# POWER.net
KiCad netlist of a schematic drawn in Altium Designer
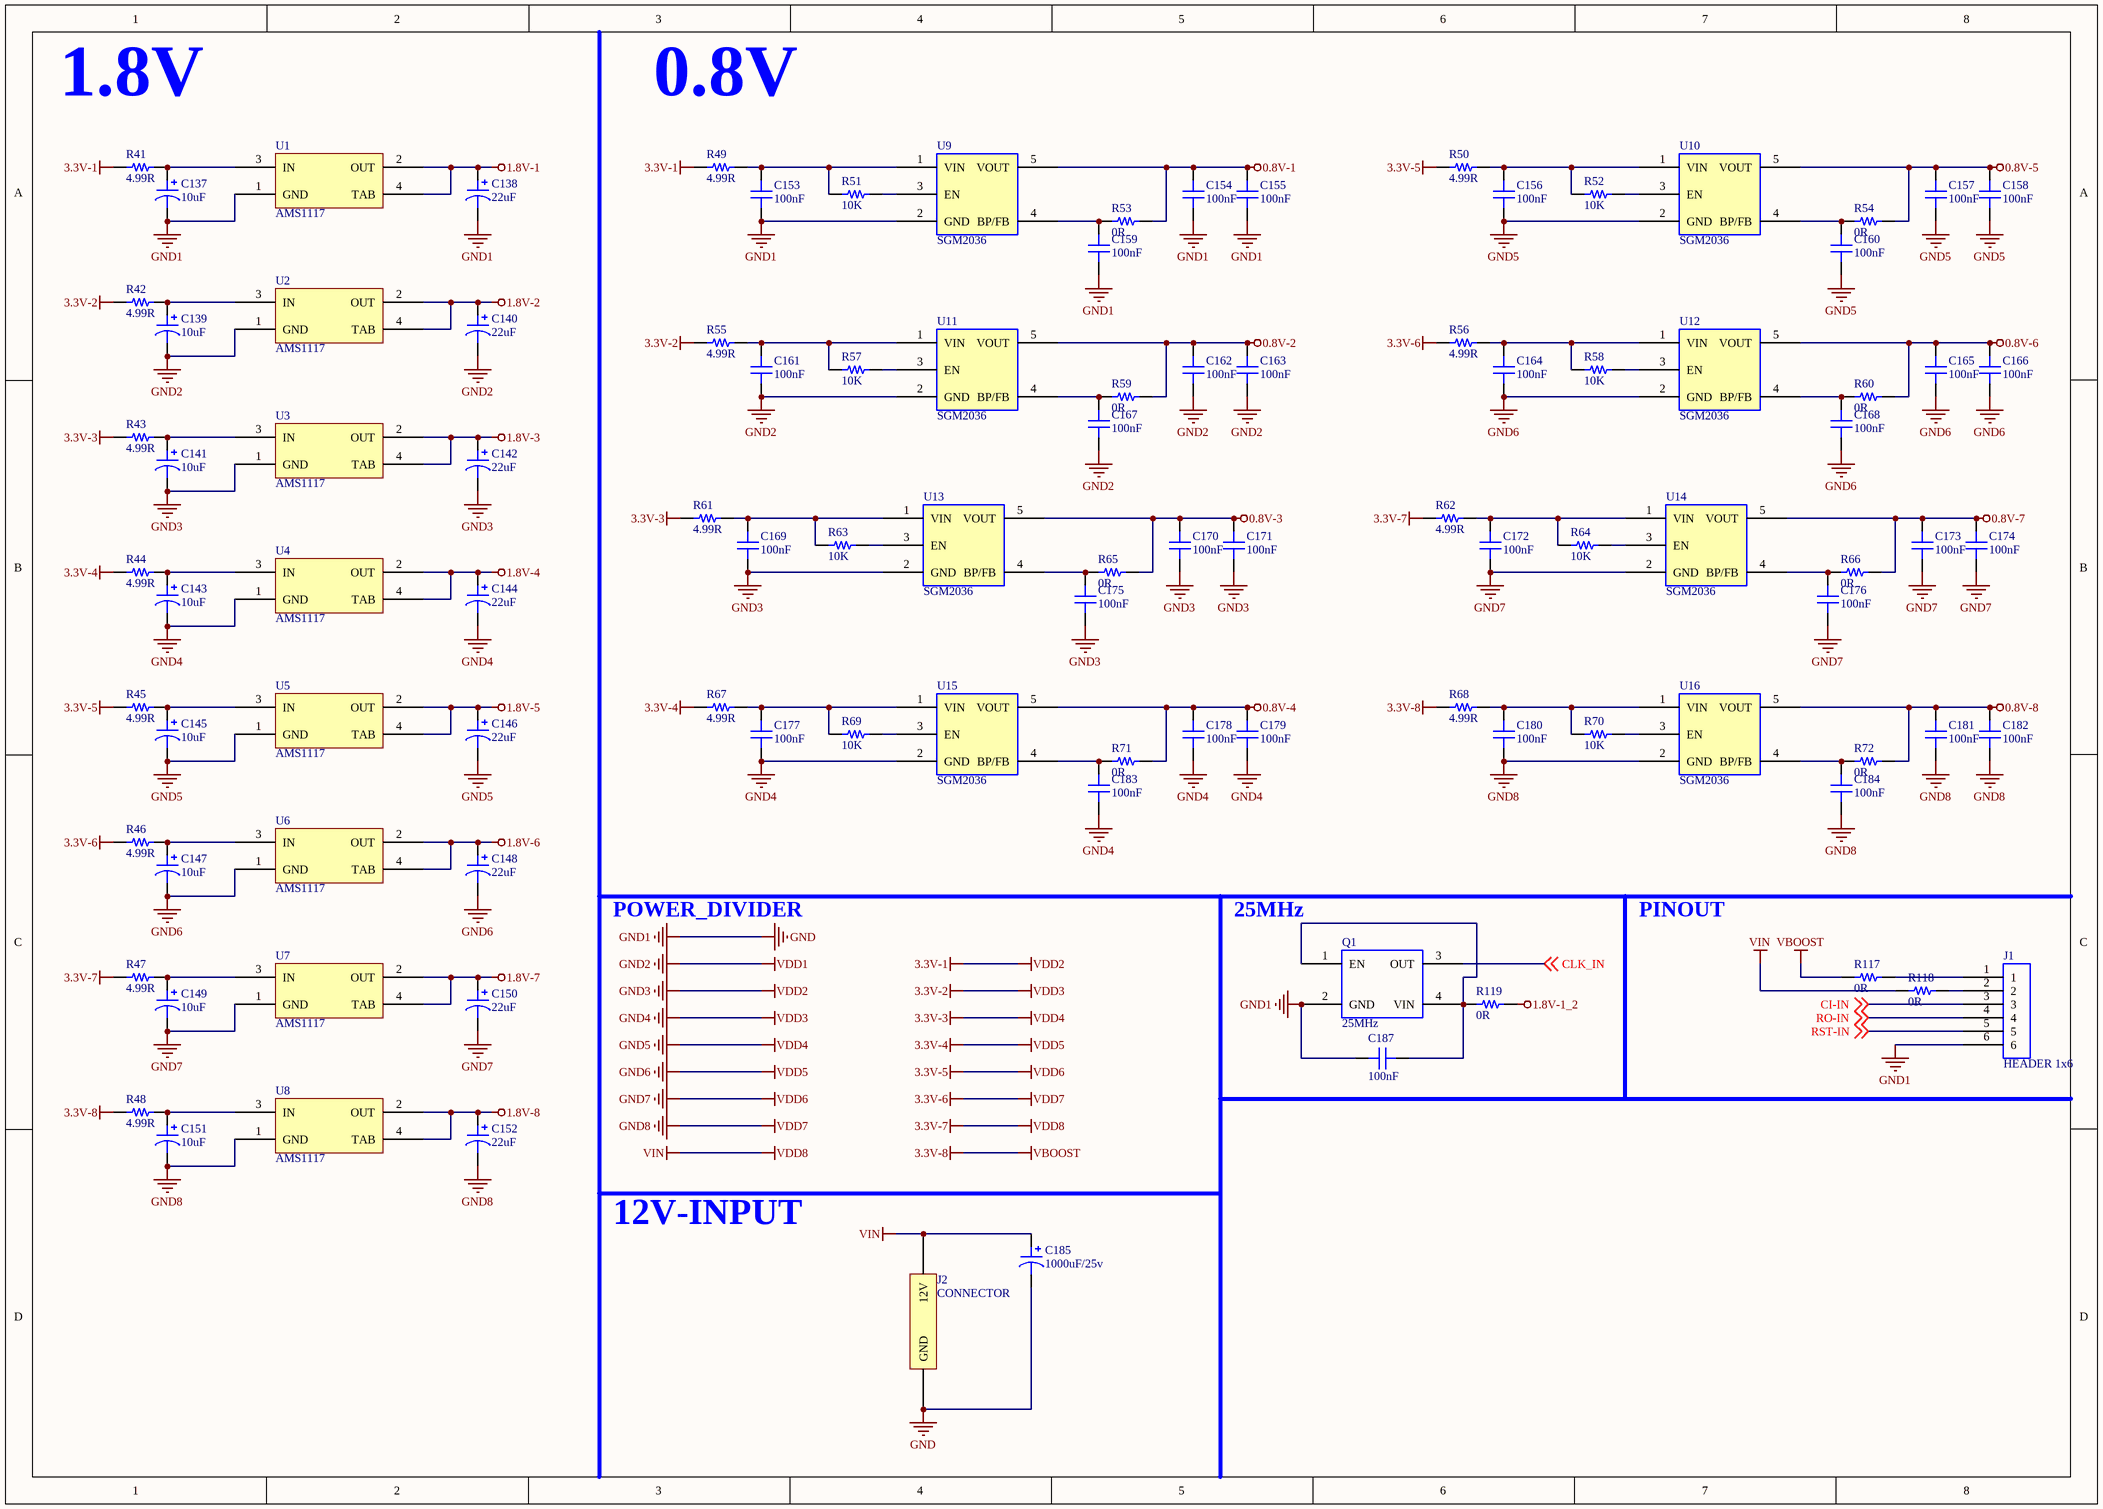
[diagram p0: POWER.SchDoc]

(export (version "E")
  (design (tool "Eeschema 10.0.6"))
  (components
    (comp (ref "C137")
      (value "10uF")
      (footprint "CAP-TAN-CASE-A")
      (libsource (lib "Miner-8Chips") (part "POLARIZED CAP"))
    )
    (comp (ref "C138")
      (value "22uF")
      (footprint "CAP-TAN-CASE-A")
      (libsource (lib "Miner-8Chips") (part "POLARIZED CAP"))
    )
    (comp (ref "C139")
      (value "10uF")
      (footprint "CAP-TAN-CASE-A")
      (libsource (lib "Miner-8Chips") (part "POLARIZED CAP"))
    )
    (comp (ref "C140")
      (value "22uF")
      (footprint "CAP-TAN-CASE-A")
      (libsource (lib "Miner-8Chips") (part "POLARIZED CAP"))
    )
    (comp (ref "C141")
      (value "10uF")
      (footprint "CAP-TAN-CASE-A")
      (libsource (lib "Miner-8Chips") (part "POLARIZED CAP"))
    )
    (comp (ref "C142")
      (value "22uF")
      (footprint "CAP-TAN-CASE-A")
      (libsource (lib "Miner-8Chips") (part "POLARIZED CAP"))
    )
    (comp (ref "C143")
      (value "10uF")
      (footprint "CAP-TAN-CASE-A")
      (libsource (lib "Miner-8Chips") (part "POLARIZED CAP"))
    )
    (comp (ref "C144")
      (value "22uF")
      (footprint "CAP-TAN-CASE-A")
      (libsource (lib "Miner-8Chips") (part "POLARIZED CAP"))
    )
    (comp (ref "C145")
      (value "10uF")
      (footprint "CAP-TAN-CASE-A")
      (libsource (lib "Miner-8Chips") (part "POLARIZED CAP"))
    )
    (comp (ref "C146")
      (value "22uF")
      (footprint "CAP-TAN-CASE-A")
      (libsource (lib "Miner-8Chips") (part "POLARIZED CAP"))
    )
    (comp (ref "C147")
      (value "10uF")
      (footprint "CAP-TAN-CASE-A")
      (libsource (lib "Miner-8Chips") (part "POLARIZED CAP"))
    )
    (comp (ref "C148")
      (value "22uF")
      (footprint "CAP-TAN-CASE-A")
      (libsource (lib "Miner-8Chips") (part "POLARIZED CAP"))
    )
    (comp (ref "C149")
      (value "10uF")
      (footprint "CAP-TAN-CASE-A")
      (libsource (lib "Miner-8Chips") (part "POLARIZED CAP"))
    )
    (comp (ref "C150")
      (value "22uF")
      (footprint "CAP-TAN-CASE-A")
      (libsource (lib "Miner-8Chips") (part "POLARIZED CAP"))
    )
    (comp (ref "C151")
      (value "10uF")
      (footprint "CAP-TAN-CASE-A")
      (libsource (lib "Miner-8Chips") (part "POLARIZED CAP"))
    )
    (comp (ref "C152")
      (value "22uF")
      (footprint "CAP-TAN-CASE-A")
      (libsource (lib "Miner-8Chips") (part "POLARIZED CAP"))
    )
    (comp (ref "C153")
      (value "100nF")
      (footprint "CAP-SMD-0402")
      (libsource (lib "Miner-8Chips") (part "CAP"))
    )
    (comp (ref "C154")
      (value "100nF")
      (footprint "CAP-SMD-0402")
      (libsource (lib "Miner-8Chips") (part "CAP"))
    )
    (comp (ref "C155")
      (value "100nF")
      (footprint "CAP-SMD-0402")
      (libsource (lib "Miner-8Chips") (part "CAP"))
    )
    (comp (ref "C156")
      (value "100nF")
      (footprint "CAP-SMD-0402")
      (libsource (lib "Miner-8Chips") (part "CAP"))
    )
    (comp (ref "C157")
      (value "100nF")
      (footprint "CAP-SMD-0402")
      (libsource (lib "Miner-8Chips") (part "CAP"))
    )
    (comp (ref "C158")
      (value "100nF")
      (footprint "CAP-SMD-0402")
      (libsource (lib "Miner-8Chips") (part "CAP"))
    )
    (comp (ref "C159")
      (value "100nF")
      (footprint "CAP-SMD-0402")
      (libsource (lib "Miner-8Chips") (part "CAP"))
    )
    (comp (ref "C160")
      (value "100nF")
      (footprint "CAP-SMD-0402")
      (libsource (lib "Miner-8Chips") (part "CAP"))
    )
    (comp (ref "C161")
      (value "100nF")
      (footprint "CAP-SMD-0402")
      (libsource (lib "Miner-8Chips") (part "CAP"))
    )
    (comp (ref "C162")
      (value "100nF")
      (footprint "CAP-SMD-0402")
      (libsource (lib "Miner-8Chips") (part "CAP"))
    )
    (comp (ref "C163")
      (value "100nF")
      (footprint "CAP-SMD-0402")
      (libsource (lib "Miner-8Chips") (part "CAP"))
    )
    (comp (ref "C164")
      (value "100nF")
      (footprint "CAP-SMD-0402")
      (libsource (lib "Miner-8Chips") (part "CAP"))
    )
    (comp (ref "C165")
      (value "100nF")
      (footprint "CAP-SMD-0402")
      (libsource (lib "Miner-8Chips") (part "CAP"))
    )
    (comp (ref "C166")
      (value "100nF")
      (footprint "CAP-SMD-0402")
      (libsource (lib "Miner-8Chips") (part "CAP"))
    )
    (comp (ref "C167")
      (value "100nF")
      (footprint "CAP-SMD-0402")
      (libsource (lib "Miner-8Chips") (part "CAP"))
    )
    (comp (ref "C168")
      (value "100nF")
      (footprint "CAP-SMD-0402")
      (libsource (lib "Miner-8Chips") (part "CAP"))
    )
    (comp (ref "C169")
      (value "100nF")
      (footprint "CAP-SMD-0402")
      (libsource (lib "Miner-8Chips") (part "CAP"))
    )
    (comp (ref "C170")
      (value "100nF")
      (footprint "CAP-SMD-0402")
      (libsource (lib "Miner-8Chips") (part "CAP"))
    )
    (comp (ref "C171")
      (value "100nF")
      (footprint "CAP-SMD-0402")
      (libsource (lib "Miner-8Chips") (part "CAP"))
    )
    (comp (ref "C172")
      (value "100nF")
      (footprint "CAP-SMD-0402")
      (libsource (lib "Miner-8Chips") (part "CAP"))
    )
    (comp (ref "C173")
      (value "100nF")
      (footprint "CAP-SMD-0402")
      (libsource (lib "Miner-8Chips") (part "CAP"))
    )
    (comp (ref "C174")
      (value "100nF")
      (footprint "CAP-SMD-0402")
      (libsource (lib "Miner-8Chips") (part "CAP"))
    )
    (comp (ref "C175")
      (value "100nF")
      (footprint "CAP-SMD-0402")
      (libsource (lib "Miner-8Chips") (part "CAP"))
    )
    (comp (ref "C176")
      (value "100nF")
      (footprint "CAP-SMD-0402")
      (libsource (lib "Miner-8Chips") (part "CAP"))
    )
    (comp (ref "C177")
      (value "100nF")
      (footprint "CAP-SMD-0402")
      (libsource (lib "Miner-8Chips") (part "CAP"))
    )
    (comp (ref "C178")
      (value "100nF")
      (footprint "CAP-SMD-0402")
      (libsource (lib "Miner-8Chips") (part "CAP"))
    )
    (comp (ref "C179")
      (value "100nF")
      (footprint "CAP-SMD-0402")
      (libsource (lib "Miner-8Chips") (part "CAP"))
    )
    (comp (ref "C180")
      (value "100nF")
      (footprint "CAP-SMD-0402")
      (libsource (lib "Miner-8Chips") (part "CAP"))
    )
    (comp (ref "C181")
      (value "100nF")
      (footprint "CAP-SMD-0402")
      (libsource (lib "Miner-8Chips") (part "CAP"))
    )
    (comp (ref "C182")
      (value "100nF")
      (footprint "CAP-SMD-0402")
      (libsource (lib "Miner-8Chips") (part "CAP"))
    )
    (comp (ref "C183")
      (value "100nF")
      (footprint "CAP-SMD-0402")
      (libsource (lib "Miner-8Chips") (part "CAP"))
    )
    (comp (ref "C184")
      (value "100nF")
      (footprint "CAP-SMD-0402")
      (libsource (lib "Miner-8Chips") (part "CAP"))
    )
    (comp (ref "C185")
      (value "1000uF/25v")
      (footprint "CAP ALUM 10.3MM")
      (libsource (lib "Miner-8Chips") (part "POLARIZED CAP"))
    )
    (comp (ref "C187")
      (value "100nF")
      (footprint "CAP-SMD-0603")
      (libsource (lib "Miner-8Chips") (part "CAP"))
    )
    (comp (ref "J1")
      (value "HEADER 1x6")
      (footprint "HEADER-1x6")
      (libsource (lib "Miner-8Chips") (part "HEADER 1x6"))
    )
    (comp (ref "J2") (value "CONNECTOR") (footprint "ATX 6") (libsource (lib "Miner-8Chips") (part "ATX 6")))
    (comp (ref "Q1") (value "25MHz") (footprint "XTALL") (libsource (lib "Miner-8Chips") (part "OSCILLATOR")))
    (comp (ref "R41")
      (value "4.99R")
      (footprint "RES-SMD-1206")
      (libsource (lib "Miner-8Chips") (part "RES"))
    )
    (comp (ref "R42")
      (value "4.99R")
      (footprint "RES-SMD-1206")
      (libsource (lib "Miner-8Chips") (part "RES"))
    )
    (comp (ref "R43")
      (value "4.99R")
      (footprint "RES-SMD-1206")
      (libsource (lib "Miner-8Chips") (part "RES"))
    )
    (comp (ref "R44")
      (value "4.99R")
      (footprint "RES-SMD-1206")
      (libsource (lib "Miner-8Chips") (part "RES"))
    )
    (comp (ref "R45")
      (value "4.99R")
      (footprint "RES-SMD-1206")
      (libsource (lib "Miner-8Chips") (part "RES"))
    )
    (comp (ref "R46")
      (value "4.99R")
      (footprint "RES-SMD-1206")
      (libsource (lib "Miner-8Chips") (part "RES"))
    )
    (comp (ref "R47")
      (value "4.99R")
      (footprint "RES-SMD-1206")
      (libsource (lib "Miner-8Chips") (part "RES"))
    )
    (comp (ref "R48")
      (value "4.99R")
      (footprint "RES-SMD-1206")
      (libsource (lib "Miner-8Chips") (part "RES"))
    )
    (comp (ref "R49")
      (value "4.99R")
      (footprint "RES-SMD-1206")
      (libsource (lib "Miner-8Chips") (part "RES"))
    )
    (comp (ref "R50")
      (value "4.99R")
      (footprint "RES-SMD-1206")
      (libsource (lib "Miner-8Chips") (part "RES"))
    )
    (comp (ref "R51") (value "10K") (footprint "RES-SMD-0402") (libsource (lib "Miner-8Chips") (part "RES")))
    (comp (ref "R52") (value "10K") (footprint "RES-SMD-0402") (libsource (lib "Miner-8Chips") (part "RES")))
    (comp (ref "R53") (value "0R") (footprint "RES-SMD-0402") (libsource (lib "Miner-8Chips") (part "RES")))
    (comp (ref "R54") (value "0R") (footprint "RES-SMD-0402") (libsource (lib "Miner-8Chips") (part "RES")))
    (comp (ref "R55")
      (value "4.99R")
      (footprint "RES-SMD-1206")
      (libsource (lib "Miner-8Chips") (part "RES"))
    )
    (comp (ref "R56")
      (value "4.99R")
      (footprint "RES-SMD-1206")
      (libsource (lib "Miner-8Chips") (part "RES"))
    )
    (comp (ref "R57") (value "10K") (footprint "RES-SMD-0402") (libsource (lib "Miner-8Chips") (part "RES")))
    (comp (ref "R58") (value "10K") (footprint "RES-SMD-0402") (libsource (lib "Miner-8Chips") (part "RES")))
    (comp (ref "R59") (value "0R") (footprint "RES-SMD-0402") (libsource (lib "Miner-8Chips") (part "RES")))
    (comp (ref "R60") (value "0R") (footprint "RES-SMD-0402") (libsource (lib "Miner-8Chips") (part "RES")))
    (comp (ref "R61")
      (value "4.99R")
      (footprint "RES-SMD-1206")
      (libsource (lib "Miner-8Chips") (part "RES"))
    )
    (comp (ref "R62")
      (value "4.99R")
      (footprint "RES-SMD-1206")
      (libsource (lib "Miner-8Chips") (part "RES"))
    )
    (comp (ref "R63") (value "10K") (footprint "RES-SMD-0402") (libsource (lib "Miner-8Chips") (part "RES")))
    (comp (ref "R64") (value "10K") (footprint "RES-SMD-0402") (libsource (lib "Miner-8Chips") (part "RES")))
    (comp (ref "R65") (value "0R") (footprint "RES-SMD-0402") (libsource (lib "Miner-8Chips") (part "RES")))
    (comp (ref "R66") (value "0R") (footprint "RES-SMD-0402") (libsource (lib "Miner-8Chips") (part "RES")))
    (comp (ref "R67")
      (value "4.99R")
      (footprint "RES-SMD-1206")
      (libsource (lib "Miner-8Chips") (part "RES"))
    )
    (comp (ref "R68")
      (value "4.99R")
      (footprint "RES-SMD-1206")
      (libsource (lib "Miner-8Chips") (part "RES"))
    )
    (comp (ref "R69") (value "10K") (footprint "RES-SMD-0402") (libsource (lib "Miner-8Chips") (part "RES")))
    (comp (ref "R70") (value "10K") (footprint "RES-SMD-0402") (libsource (lib "Miner-8Chips") (part "RES")))
    (comp (ref "R71") (value "0R") (footprint "RES-SMD-0402") (libsource (lib "Miner-8Chips") (part "RES")))
    (comp (ref "R72") (value "0R") (footprint "RES-SMD-0402") (libsource (lib "Miner-8Chips") (part "RES")))
    (comp (ref "R117") (value "0R") (footprint "RES") (libsource (lib "Miner-8Chips") (part "RES")))
    (comp (ref "R118") (value "0R") (footprint "RES") (libsource (lib "Miner-8Chips") (part "RES")))
    (comp (ref "R119") (value "0R") (footprint "RES") (libsource (lib "Miner-8Chips") (part "RES")))
    (comp (ref "U1")
      (value "AMS1117")
      (footprint "AMS1117")
      (libsource (lib "Miner-8Chips") (part "AMS1117"))
    )
    (comp (ref "U2")
      (value "AMS1117")
      (footprint "AMS1117")
      (libsource (lib "Miner-8Chips") (part "AMS1117"))
    )
    (comp (ref "U3")
      (value "AMS1117")
      (footprint "AMS1117")
      (libsource (lib "Miner-8Chips") (part "AMS1117"))
    )
    (comp (ref "U4")
      (value "AMS1117")
      (footprint "AMS1117")
      (libsource (lib "Miner-8Chips") (part "AMS1117"))
    )
    (comp (ref "U5")
      (value "AMS1117")
      (footprint "AMS1117")
      (libsource (lib "Miner-8Chips") (part "AMS1117"))
    )
    (comp (ref "U6")
      (value "AMS1117")
      (footprint "AMS1117")
      (libsource (lib "Miner-8Chips") (part "AMS1117"))
    )
    (comp (ref "U7")
      (value "AMS1117")
      (footprint "AMS1117")
      (libsource (lib "Miner-8Chips") (part "AMS1117"))
    )
    (comp (ref "U8")
      (value "AMS1117")
      (footprint "AMS1117")
      (libsource (lib "Miner-8Chips") (part "AMS1117"))
    )
    (comp (ref "U9")
      (value "SGM2036")
      (footprint "SOT23-5PIN")
      (libsource (lib "Miner-8Chips") (part "SGM2036"))
    )
    (comp (ref "U10")
      (value "SGM2036")
      (footprint "SOT23-5PIN")
      (libsource (lib "Miner-8Chips") (part "SGM2036"))
    )
    (comp (ref "U11")
      (value "SGM2036")
      (footprint "SOT23-5PIN")
      (libsource (lib "Miner-8Chips") (part "SGM2036"))
    )
    (comp (ref "U12")
      (value "SGM2036")
      (footprint "SOT23-5PIN")
      (libsource (lib "Miner-8Chips") (part "SGM2036"))
    )
    (comp (ref "U13")
      (value "SGM2036")
      (footprint "SOT23-5PIN")
      (libsource (lib "Miner-8Chips") (part "SGM2036"))
    )
    (comp (ref "U14")
      (value "SGM2036")
      (footprint "SOT23-5PIN")
      (libsource (lib "Miner-8Chips") (part "SGM2036"))
    )
    (comp (ref "U15")
      (value "SGM2036")
      (footprint "SOT23-5PIN")
      (libsource (lib "Miner-8Chips") (part "SGM2036"))
    )
    (comp (ref "U16")
      (value "SGM2036")
      (footprint "SOT23-5PIN")
      (libsource (lib "Miner-8Chips") (part "SGM2036"))
    )
  )
  (nets
    (net (code "1") (name "0.8V-1") (class "Default")
      (node (ref "C154") (pin "2") (pinfunction "2_2") (pintype "passive"))
      (node (ref "C155") (pin "2") (pinfunction "2_2") (pintype "passive"))
      (node (ref "R53") (pin "2") (pinfunction "2_2") (pintype "passive"))
      (node (ref "U9") (pin "5") (pinfunction "VOUT_5") (pintype "passive"))
    )
    (net (code "2") (name "0.8V-2") (class "Default")
      (node (ref "C162") (pin "2") (pinfunction "2_2") (pintype "passive"))
      (node (ref "C163") (pin "2") (pinfunction "2_2") (pintype "passive"))
      (node (ref "R59") (pin "2") (pinfunction "2_2") (pintype "passive"))
      (node (ref "U11") (pin "5") (pinfunction "VOUT_5") (pintype "passive"))
    )
    (net (code "3") (name "0.8V-3") (class "Default")
      (node (ref "C170") (pin "2") (pinfunction "2_2") (pintype "passive"))
      (node (ref "C171") (pin "2") (pinfunction "2_2") (pintype "passive"))
      (node (ref "R65") (pin "2") (pinfunction "2_2") (pintype "passive"))
      (node (ref "U13") (pin "5") (pinfunction "VOUT_5") (pintype "passive"))
    )
    (net (code "4") (name "0.8V-4") (class "Default")
      (node (ref "C178") (pin "2") (pinfunction "2_2") (pintype "passive"))
      (node (ref "C179") (pin "2") (pinfunction "2_2") (pintype "passive"))
      (node (ref "R71") (pin "2") (pinfunction "2_2") (pintype "passive"))
      (node (ref "U15") (pin "5") (pinfunction "VOUT_5") (pintype "passive"))
    )
    (net (code "5") (name "0.8V-5") (class "Default")
      (node (ref "C157") (pin "2") (pinfunction "2_2") (pintype "passive"))
      (node (ref "C158") (pin "2") (pinfunction "2_2") (pintype "passive"))
      (node (ref "R54") (pin "2") (pinfunction "2_2") (pintype "passive"))
      (node (ref "U10") (pin "5") (pinfunction "VOUT_5") (pintype "passive"))
    )
    (net (code "6") (name "0.8V-6") (class "Default")
      (node (ref "C165") (pin "2") (pinfunction "2_2") (pintype "passive"))
      (node (ref "C166") (pin "2") (pinfunction "2_2") (pintype "passive"))
      (node (ref "R60") (pin "2") (pinfunction "2_2") (pintype "passive"))
      (node (ref "U12") (pin "5") (pinfunction "VOUT_5") (pintype "passive"))
    )
    (net (code "7") (name "0.8V-7") (class "Default")
      (node (ref "C173") (pin "2") (pinfunction "2_2") (pintype "passive"))
      (node (ref "C174") (pin "2") (pinfunction "2_2") (pintype "passive"))
      (node (ref "R66") (pin "2") (pinfunction "2_2") (pintype "passive"))
      (node (ref "U14") (pin "5") (pinfunction "VOUT_5") (pintype "passive"))
    )
    (net (code "8") (name "0.8V-8") (class "Default")
      (node (ref "C181") (pin "2") (pinfunction "2_2") (pintype "passive"))
      (node (ref "C182") (pin "2") (pinfunction "2_2") (pintype "passive"))
      (node (ref "R72") (pin "2") (pinfunction "2_2") (pintype "passive"))
      (node (ref "U16") (pin "5") (pinfunction "VOUT_5") (pintype "passive"))
    )
    (net (code "9") (name "1.8V-1") (class "Default")
      (node (ref "C138") (pin "1") (pinfunction "1_1") (pintype "passive"))
      (node (ref "U1") (pin "2") (pinfunction "OUT_2") (pintype "passive"))
      (node (ref "U1") (pin "4") (pinfunction "TAB_4") (pintype "passive"))
    )
    (net (code "10") (name "1.8V-1_2") (class "Default")
      (node (ref "R119") (pin "2") (pinfunction "2_2") (pintype "passive"))
    )
    (net (code "11") (name "1.8V-2") (class "Default")
      (node (ref "C140") (pin "1") (pinfunction "1_1") (pintype "passive"))
      (node (ref "U2") (pin "2") (pinfunction "OUT_2") (pintype "passive"))
      (node (ref "U2") (pin "4") (pinfunction "TAB_4") (pintype "passive"))
    )
    (net (code "12") (name "1.8V-3") (class "Default")
      (node (ref "C142") (pin "1") (pinfunction "1_1") (pintype "passive"))
      (node (ref "U3") (pin "2") (pinfunction "OUT_2") (pintype "passive"))
      (node (ref "U3") (pin "4") (pinfunction "TAB_4") (pintype "passive"))
    )
    (net (code "13") (name "1.8V-4") (class "Default")
      (node (ref "C144") (pin "1") (pinfunction "1_1") (pintype "passive"))
      (node (ref "U4") (pin "2") (pinfunction "OUT_2") (pintype "passive"))
      (node (ref "U4") (pin "4") (pinfunction "TAB_4") (pintype "passive"))
    )
    (net (code "14") (name "1.8V-5") (class "Default")
      (node (ref "C146") (pin "1") (pinfunction "1_1") (pintype "passive"))
      (node (ref "U5") (pin "2") (pinfunction "OUT_2") (pintype "passive"))
      (node (ref "U5") (pin "4") (pinfunction "TAB_4") (pintype "passive"))
    )
    (net (code "15") (name "1.8V-6") (class "Default")
      (node (ref "C148") (pin "1") (pinfunction "1_1") (pintype "passive"))
      (node (ref "U6") (pin "2") (pinfunction "OUT_2") (pintype "passive"))
      (node (ref "U6") (pin "4") (pinfunction "TAB_4") (pintype "passive"))
    )
    (net (code "16") (name "1.8V-7") (class "Default")
      (node (ref "C150") (pin "1") (pinfunction "1_1") (pintype "passive"))
      (node (ref "U7") (pin "2") (pinfunction "OUT_2") (pintype "passive"))
      (node (ref "U7") (pin "4") (pinfunction "TAB_4") (pintype "passive"))
    )
    (net (code "17") (name "1.8V-8") (class "Default")
      (node (ref "C152") (pin "1") (pinfunction "1_1") (pintype "passive"))
      (node (ref "U8") (pin "2") (pinfunction "OUT_2") (pintype "passive"))
      (node (ref "U8") (pin "4") (pinfunction "TAB_4") (pintype "passive"))
    )
    (net (code "18") (name "3.3V-1") (class "Default")
      (node (ref "C141") (pin "2") (pinfunction "2_2") (pintype "passive"))
      (node (ref "C142") (pin "2") (pinfunction "2_2") (pintype "passive"))
      (node (ref "C169") (pin "1") (pinfunction "1_1") (pintype "passive"))
      (node (ref "C170") (pin "1") (pinfunction "1_1") (pintype "passive"))
      (node (ref "C171") (pin "1") (pinfunction "1_1") (pintype "passive"))
      (node (ref "C175") (pin "1") (pinfunction "1_1") (pintype "passive"))
      (node (ref "R41") (pin "1") (pinfunction "1_1") (pintype "passive"))
      (node (ref "R49") (pin "1") (pinfunction "1_1") (pintype "passive"))
      (node (ref "U13") (pin "2") (pinfunction "GND_2") (pintype "passive"))
      (node (ref "U3") (pin "1") (pinfunction "GND_1") (pintype "passive"))
    )
    (net (code "19") (name "3.3V-2") (class "Default")
      (node (ref "C143") (pin "2") (pinfunction "2_2") (pintype "passive"))
      (node (ref "C144") (pin "2") (pinfunction "2_2") (pintype "passive"))
      (node (ref "C177") (pin "1") (pinfunction "1_1") (pintype "passive"))
      (node (ref "C178") (pin "1") (pinfunction "1_1") (pintype "passive"))
      (node (ref "C179") (pin "1") (pinfunction "1_1") (pintype "passive"))
      (node (ref "C183") (pin "1") (pinfunction "1_1") (pintype "passive"))
      (node (ref "R42") (pin "1") (pinfunction "1_1") (pintype "passive"))
      (node (ref "R55") (pin "1") (pinfunction "1_1") (pintype "passive"))
      (node (ref "U15") (pin "2") (pinfunction "GND_2") (pintype "passive"))
      (node (ref "U4") (pin "1") (pinfunction "GND_1") (pintype "passive"))
    )
    (net (code "20") (name "3.3V-3") (class "Default")
      (node (ref "C145") (pin "2") (pinfunction "2_2") (pintype "passive"))
      (node (ref "C146") (pin "2") (pinfunction "2_2") (pintype "passive"))
      (node (ref "C156") (pin "1") (pinfunction "1_1") (pintype "passive"))
      (node (ref "C157") (pin "1") (pinfunction "1_1") (pintype "passive"))
      (node (ref "C158") (pin "1") (pinfunction "1_1") (pintype "passive"))
      (node (ref "C160") (pin "1") (pinfunction "1_1") (pintype "passive"))
      (node (ref "R43") (pin "1") (pinfunction "1_1") (pintype "passive"))
      (node (ref "R61") (pin "1") (pinfunction "1_1") (pintype "passive"))
      (node (ref "U10") (pin "2") (pinfunction "GND_2") (pintype "passive"))
      (node (ref "U5") (pin "1") (pinfunction "GND_1") (pintype "passive"))
    )
    (net (code "21") (name "3.3V-4") (class "Default")
      (node (ref "C147") (pin "2") (pinfunction "2_2") (pintype "passive"))
      (node (ref "C148") (pin "2") (pinfunction "2_2") (pintype "passive"))
      (node (ref "C164") (pin "1") (pinfunction "1_1") (pintype "passive"))
      (node (ref "C165") (pin "1") (pinfunction "1_1") (pintype "passive"))
      (node (ref "C166") (pin "1") (pinfunction "1_1") (pintype "passive"))
      (node (ref "C168") (pin "1") (pinfunction "1_1") (pintype "passive"))
      (node (ref "R44") (pin "1") (pinfunction "1_1") (pintype "passive"))
      (node (ref "R67") (pin "1") (pinfunction "1_1") (pintype "passive"))
      (node (ref "U12") (pin "2") (pinfunction "GND_2") (pintype "passive"))
      (node (ref "U6") (pin "1") (pinfunction "GND_1") (pintype "passive"))
    )
    (net (code "22") (name "3.3V-5") (class "Default")
      (node (ref "C149") (pin "2") (pinfunction "2_2") (pintype "passive"))
      (node (ref "C150") (pin "2") (pinfunction "2_2") (pintype "passive"))
      (node (ref "C172") (pin "1") (pinfunction "1_1") (pintype "passive"))
      (node (ref "C173") (pin "1") (pinfunction "1_1") (pintype "passive"))
      (node (ref "C174") (pin "1") (pinfunction "1_1") (pintype "passive"))
      (node (ref "C176") (pin "1") (pinfunction "1_1") (pintype "passive"))
      (node (ref "R45") (pin "1") (pinfunction "1_1") (pintype "passive"))
      (node (ref "R50") (pin "1") (pinfunction "1_1") (pintype "passive"))
      (node (ref "U14") (pin "2") (pinfunction "GND_2") (pintype "passive"))
      (node (ref "U7") (pin "1") (pinfunction "GND_1") (pintype "passive"))
    )
    (net (code "23") (name "3.3V-6") (class "Default")
      (node (ref "C151") (pin "2") (pinfunction "2_2") (pintype "passive"))
      (node (ref "C152") (pin "2") (pinfunction "2_2") (pintype "passive"))
      (node (ref "C180") (pin "1") (pinfunction "1_1") (pintype "passive"))
      (node (ref "C181") (pin "1") (pinfunction "1_1") (pintype "passive"))
      (node (ref "C182") (pin "1") (pinfunction "1_1") (pintype "passive"))
      (node (ref "C184") (pin "1") (pinfunction "1_1") (pintype "passive"))
      (node (ref "R46") (pin "1") (pinfunction "1_1") (pintype "passive"))
      (node (ref "R56") (pin "1") (pinfunction "1_1") (pintype "passive"))
      (node (ref "U16") (pin "2") (pinfunction "GND_2") (pintype "passive"))
      (node (ref "U8") (pin "1") (pinfunction "GND_1") (pintype "passive"))
    )
    (net (code "24") (name "3.3V-7") (class "Default")
      (node (ref "C185") (pin "1") (pinfunction "1_1") (pintype "passive"))
      (node (ref "J2") (pin "2") (pinfunction "12V_2") (pintype "passive"))
      (node (ref "R118") (pin "1") (pinfunction "1_1") (pintype "passive"))
      (node (ref "R47") (pin "1") (pinfunction "1_1") (pintype "passive"))
      (node (ref "R62") (pin "1") (pinfunction "1_1") (pintype "passive"))
    )
    (net (code "25") (name "3.3V-8") (class "Default")
      (node (ref "R117") (pin "1") (pinfunction "1_1") (pintype "passive"))
      (node (ref "R48") (pin "1") (pinfunction "1_1") (pintype "passive"))
      (node (ref "R68") (pin "1") (pinfunction "1_1") (pintype "passive"))
    )
    (net (code "26") (name "CI-IN") (class "Default")
      (node (ref "J1") (pin "3") (pinfunction "3_3") (pintype "passive"))
    )
    (net (code "27") (name "CLK_IN") (class "Default")
      (node (ref "Q1") (pin "3") (pinfunction "OUT_3") (pintype "passive"))
    )
    (net (code "28") (name "GND") (class "Default")
      (node (ref "C137") (pin "2") (pinfunction "2_2") (pintype "passive"))
      (node (ref "C138") (pin "2") (pinfunction "2_2") (pintype "passive"))
      (node (ref "C153") (pin "1") (pinfunction "1_1") (pintype "passive"))
      (node (ref "C154") (pin "1") (pinfunction "1_1") (pintype "passive"))
      (node (ref "C155") (pin "1") (pinfunction "1_1") (pintype "passive"))
      (node (ref "C159") (pin "1") (pinfunction "1_1") (pintype "passive"))
      (node (ref "C185") (pin "2") (pinfunction "2_2") (pintype "passive"))
      (node (ref "C187") (pin "2") (pinfunction "2_2") (pintype "passive"))
      (node (ref "J1") (pin "6") (pinfunction "6_6") (pintype "passive"))
      (node (ref "J2") (pin "1") (pinfunction "GND_1") (pintype "passive"))
      (node (ref "Q1") (pin "2") (pinfunction "GND_2") (pintype "passive"))
      (node (ref "U1") (pin "1") (pinfunction "GND_1") (pintype "passive"))
      (node (ref "U9") (pin "2") (pinfunction "GND_2") (pintype "passive"))
    )
    (net (code "29") (name "GND2") (class "Default")
      (node (ref "C139") (pin "2") (pinfunction "2_2") (pintype "passive"))
      (node (ref "C140") (pin "2") (pinfunction "2_2") (pintype "passive"))
      (node (ref "C161") (pin "1") (pinfunction "1_1") (pintype "passive"))
      (node (ref "C162") (pin "1") (pinfunction "1_1") (pintype "passive"))
      (node (ref "C163") (pin "1") (pinfunction "1_1") (pintype "passive"))
      (node (ref "C167") (pin "1") (pinfunction "1_1") (pintype "passive"))
      (node (ref "U11") (pin "2") (pinfunction "GND_2") (pintype "passive"))
      (node (ref "U2") (pin "1") (pinfunction "GND_1") (pintype "passive"))
    )
    (net (code "30") (name "Net-(J1-Pad1)") (class "Default")
      (node (ref "J1") (pin "1") (pinfunction "1_1") (pintype "passive"))
      (node (ref "R117") (pin "2") (pinfunction "2_2") (pintype "passive"))
    )
    (net (code "31") (name "Net-(J1-Pad2)") (class "Default")
      (node (ref "J1") (pin "2") (pinfunction "2_2") (pintype "passive"))
      (node (ref "R118") (pin "2") (pinfunction "2_2") (pintype "passive"))
    )
    (net (code "32") (name "Net-(Q1-EN)") (class "Default")
      (node (ref "C187") (pin "1") (pinfunction "1_1") (pintype "passive"))
      (node (ref "Q1") (pin "1") (pinfunction "EN_1") (pintype "passive"))
      (node (ref "Q1") (pin "4") (pinfunction "VIN_4") (pintype "passive"))
      (node (ref "R119") (pin "1") (pinfunction "1_1") (pintype "passive"))
    )
    (net (code "33") (name "Net-(U1-IN)") (class "Default")
      (node (ref "C137") (pin "1") (pinfunction "1_1") (pintype "passive"))
      (node (ref "R41") (pin "2") (pinfunction "2_2") (pintype "passive"))
      (node (ref "U1") (pin "3") (pinfunction "IN_3") (pintype "passive"))
    )
    (net (code "34") (name "Net-(U2-IN)") (class "Default")
      (node (ref "C139") (pin "1") (pinfunction "1_1") (pintype "passive"))
      (node (ref "R42") (pin "2") (pinfunction "2_2") (pintype "passive"))
      (node (ref "U2") (pin "3") (pinfunction "IN_3") (pintype "passive"))
    )
    (net (code "35") (name "Net-(U3-IN)") (class "Default")
      (node (ref "C141") (pin "1") (pinfunction "1_1") (pintype "passive"))
      (node (ref "R43") (pin "2") (pinfunction "2_2") (pintype "passive"))
      (node (ref "U3") (pin "3") (pinfunction "IN_3") (pintype "passive"))
    )
    (net (code "36") (name "Net-(U4-IN)") (class "Default")
      (node (ref "C143") (pin "1") (pinfunction "1_1") (pintype "passive"))
      (node (ref "R44") (pin "2") (pinfunction "2_2") (pintype "passive"))
      (node (ref "U4") (pin "3") (pinfunction "IN_3") (pintype "passive"))
    )
    (net (code "37") (name "Net-(U5-IN)") (class "Default")
      (node (ref "C145") (pin "1") (pinfunction "1_1") (pintype "passive"))
      (node (ref "R45") (pin "2") (pinfunction "2_2") (pintype "passive"))
      (node (ref "U5") (pin "3") (pinfunction "IN_3") (pintype "passive"))
    )
    (net (code "38") (name "Net-(U6-IN)") (class "Default")
      (node (ref "C147") (pin "1") (pinfunction "1_1") (pintype "passive"))
      (node (ref "R46") (pin "2") (pinfunction "2_2") (pintype "passive"))
      (node (ref "U6") (pin "3") (pinfunction "IN_3") (pintype "passive"))
    )
    (net (code "39") (name "Net-(U7-IN)") (class "Default")
      (node (ref "C149") (pin "1") (pinfunction "1_1") (pintype "passive"))
      (node (ref "R47") (pin "2") (pinfunction "2_2") (pintype "passive"))
      (node (ref "U7") (pin "3") (pinfunction "IN_3") (pintype "passive"))
    )
    (net (code "40") (name "Net-(U8-IN)") (class "Default")
      (node (ref "C151") (pin "1") (pinfunction "1_1") (pintype "passive"))
      (node (ref "R48") (pin "2") (pinfunction "2_2") (pintype "passive"))
      (node (ref "U8") (pin "3") (pinfunction "IN_3") (pintype "passive"))
    )
    (net (code "41") (name "Net-(U9-BP{slash}FB)") (class "Default")
      (node (ref "C159") (pin "2") (pinfunction "2_2") (pintype "passive"))
      (node (ref "R53") (pin "1") (pinfunction "1_1") (pintype "passive"))
      (node (ref "U9") (pin "4") (pinfunction "BP/FB_4") (pintype "passive"))
    )
    (net (code "42") (name "Net-(U9-EN)") (class "Default")
      (node (ref "R51") (pin "2") (pinfunction "2_2") (pintype "passive"))
      (node (ref "U9") (pin "3") (pinfunction "EN_3") (pintype "passive"))
    )
    (net (code "43") (name "Net-(U9-VIN)") (class "Default")
      (node (ref "C153") (pin "2") (pinfunction "2_2") (pintype "passive"))
      (node (ref "R49") (pin "2") (pinfunction "2_2") (pintype "passive"))
      (node (ref "R51") (pin "1") (pinfunction "1_1") (pintype "passive"))
      (node (ref "U9") (pin "1") (pinfunction "VIN_1") (pintype "passive"))
    )
    (net (code "44") (name "Net-(U10-BP{slash}FB)") (class "Default")
      (node (ref "C160") (pin "2") (pinfunction "2_2") (pintype "passive"))
      (node (ref "R54") (pin "1") (pinfunction "1_1") (pintype "passive"))
      (node (ref "U10") (pin "4") (pinfunction "BP/FB_4") (pintype "passive"))
    )
    (net (code "45") (name "Net-(U10-EN)") (class "Default")
      (node (ref "R52") (pin "2") (pinfunction "2_2") (pintype "passive"))
      (node (ref "U10") (pin "3") (pinfunction "EN_3") (pintype "passive"))
    )
    (net (code "46") (name "Net-(U10-VIN)") (class "Default")
      (node (ref "C156") (pin "2") (pinfunction "2_2") (pintype "passive"))
      (node (ref "R50") (pin "2") (pinfunction "2_2") (pintype "passive"))
      (node (ref "R52") (pin "1") (pinfunction "1_1") (pintype "passive"))
      (node (ref "U10") (pin "1") (pinfunction "VIN_1") (pintype "passive"))
    )
    (net (code "47") (name "Net-(U11-BP{slash}FB)") (class "Default")
      (node (ref "C167") (pin "2") (pinfunction "2_2") (pintype "passive"))
      (node (ref "R59") (pin "1") (pinfunction "1_1") (pintype "passive"))
      (node (ref "U11") (pin "4") (pinfunction "BP/FB_4") (pintype "passive"))
    )
    (net (code "48") (name "Net-(U11-EN)") (class "Default")
      (node (ref "R57") (pin "2") (pinfunction "2_2") (pintype "passive"))
      (node (ref "U11") (pin "3") (pinfunction "EN_3") (pintype "passive"))
    )
    (net (code "49") (name "Net-(U11-VIN)") (class "Default")
      (node (ref "C161") (pin "2") (pinfunction "2_2") (pintype "passive"))
      (node (ref "R55") (pin "2") (pinfunction "2_2") (pintype "passive"))
      (node (ref "R57") (pin "1") (pinfunction "1_1") (pintype "passive"))
      (node (ref "U11") (pin "1") (pinfunction "VIN_1") (pintype "passive"))
    )
    (net (code "50") (name "Net-(U12-BP{slash}FB)") (class "Default")
      (node (ref "C168") (pin "2") (pinfunction "2_2") (pintype "passive"))
      (node (ref "R60") (pin "1") (pinfunction "1_1") (pintype "passive"))
      (node (ref "U12") (pin "4") (pinfunction "BP/FB_4") (pintype "passive"))
    )
    (net (code "51") (name "Net-(U12-EN)") (class "Default")
      (node (ref "R58") (pin "2") (pinfunction "2_2") (pintype "passive"))
      (node (ref "U12") (pin "3") (pinfunction "EN_3") (pintype "passive"))
    )
    (net (code "52") (name "Net-(U12-VIN)") (class "Default")
      (node (ref "C164") (pin "2") (pinfunction "2_2") (pintype "passive"))
      (node (ref "R56") (pin "2") (pinfunction "2_2") (pintype "passive"))
      (node (ref "R58") (pin "1") (pinfunction "1_1") (pintype "passive"))
      (node (ref "U12") (pin "1") (pinfunction "VIN_1") (pintype "passive"))
    )
    (net (code "53") (name "Net-(U13-BP{slash}FB)") (class "Default")
      (node (ref "C175") (pin "2") (pinfunction "2_2") (pintype "passive"))
      (node (ref "R65") (pin "1") (pinfunction "1_1") (pintype "passive"))
      (node (ref "U13") (pin "4") (pinfunction "BP/FB_4") (pintype "passive"))
    )
    (net (code "54") (name "Net-(U13-EN)") (class "Default")
      (node (ref "R63") (pin "2") (pinfunction "2_2") (pintype "passive"))
      (node (ref "U13") (pin "3") (pinfunction "EN_3") (pintype "passive"))
    )
    (net (code "55") (name "Net-(U13-VIN)") (class "Default")
      (node (ref "C169") (pin "2") (pinfunction "2_2") (pintype "passive"))
      (node (ref "R61") (pin "2") (pinfunction "2_2") (pintype "passive"))
      (node (ref "R63") (pin "1") (pinfunction "1_1") (pintype "passive"))
      (node (ref "U13") (pin "1") (pinfunction "VIN_1") (pintype "passive"))
    )
    (net (code "56") (name "Net-(U14-BP{slash}FB)") (class "Default")
      (node (ref "C176") (pin "2") (pinfunction "2_2") (pintype "passive"))
      (node (ref "R66") (pin "1") (pinfunction "1_1") (pintype "passive"))
      (node (ref "U14") (pin "4") (pinfunction "BP/FB_4") (pintype "passive"))
    )
    (net (code "57") (name "Net-(U14-EN)") (class "Default")
      (node (ref "R64") (pin "2") (pinfunction "2_2") (pintype "passive"))
      (node (ref "U14") (pin "3") (pinfunction "EN_3") (pintype "passive"))
    )
    (net (code "58") (name "Net-(U14-VIN)") (class "Default")
      (node (ref "C172") (pin "2") (pinfunction "2_2") (pintype "passive"))
      (node (ref "R62") (pin "2") (pinfunction "2_2") (pintype "passive"))
      (node (ref "R64") (pin "1") (pinfunction "1_1") (pintype "passive"))
      (node (ref "U14") (pin "1") (pinfunction "VIN_1") (pintype "passive"))
    )
    (net (code "59") (name "Net-(U15-BP{slash}FB)") (class "Default")
      (node (ref "C183") (pin "2") (pinfunction "2_2") (pintype "passive"))
      (node (ref "R71") (pin "1") (pinfunction "1_1") (pintype "passive"))
      (node (ref "U15") (pin "4") (pinfunction "BP/FB_4") (pintype "passive"))
    )
    (net (code "60") (name "Net-(U15-EN)") (class "Default")
      (node (ref "R69") (pin "2") (pinfunction "2_2") (pintype "passive"))
      (node (ref "U15") (pin "3") (pinfunction "EN_3") (pintype "passive"))
    )
    (net (code "61") (name "Net-(U15-VIN)") (class "Default")
      (node (ref "C177") (pin "2") (pinfunction "2_2") (pintype "passive"))
      (node (ref "R67") (pin "2") (pinfunction "2_2") (pintype "passive"))
      (node (ref "R69") (pin "1") (pinfunction "1_1") (pintype "passive"))
      (node (ref "U15") (pin "1") (pinfunction "VIN_1") (pintype "passive"))
    )
    (net (code "62") (name "Net-(U16-BP{slash}FB)") (class "Default")
      (node (ref "C184") (pin "2") (pinfunction "2_2") (pintype "passive"))
      (node (ref "R72") (pin "1") (pinfunction "1_1") (pintype "passive"))
      (node (ref "U16") (pin "4") (pinfunction "BP/FB_4") (pintype "passive"))
    )
    (net (code "63") (name "Net-(U16-EN)") (class "Default")
      (node (ref "R70") (pin "2") (pinfunction "2_2") (pintype "passive"))
      (node (ref "U16") (pin "3") (pinfunction "EN_3") (pintype "passive"))
    )
    (net (code "64") (name "Net-(U16-VIN)") (class "Default")
      (node (ref "C180") (pin "2") (pinfunction "2_2") (pintype "passive"))
      (node (ref "R68") (pin "2") (pinfunction "2_2") (pintype "passive"))
      (node (ref "R70") (pin "1") (pinfunction "1_1") (pintype "passive"))
      (node (ref "U16") (pin "1") (pinfunction "VIN_1") (pintype "passive"))
    )
    (net (code "65") (name "RO-IN") (class "Default")
      (node (ref "J1") (pin "4") (pinfunction "4_4") (pintype "passive"))
    )
    (net (code "66") (name "RST-IN") (class "Default")
      (node (ref "J1") (pin "5") (pinfunction "5_5") (pintype "passive"))
    )
  )
)
